# Connectors.net
KiCad netlist of a schematic drawn in Altium Designer
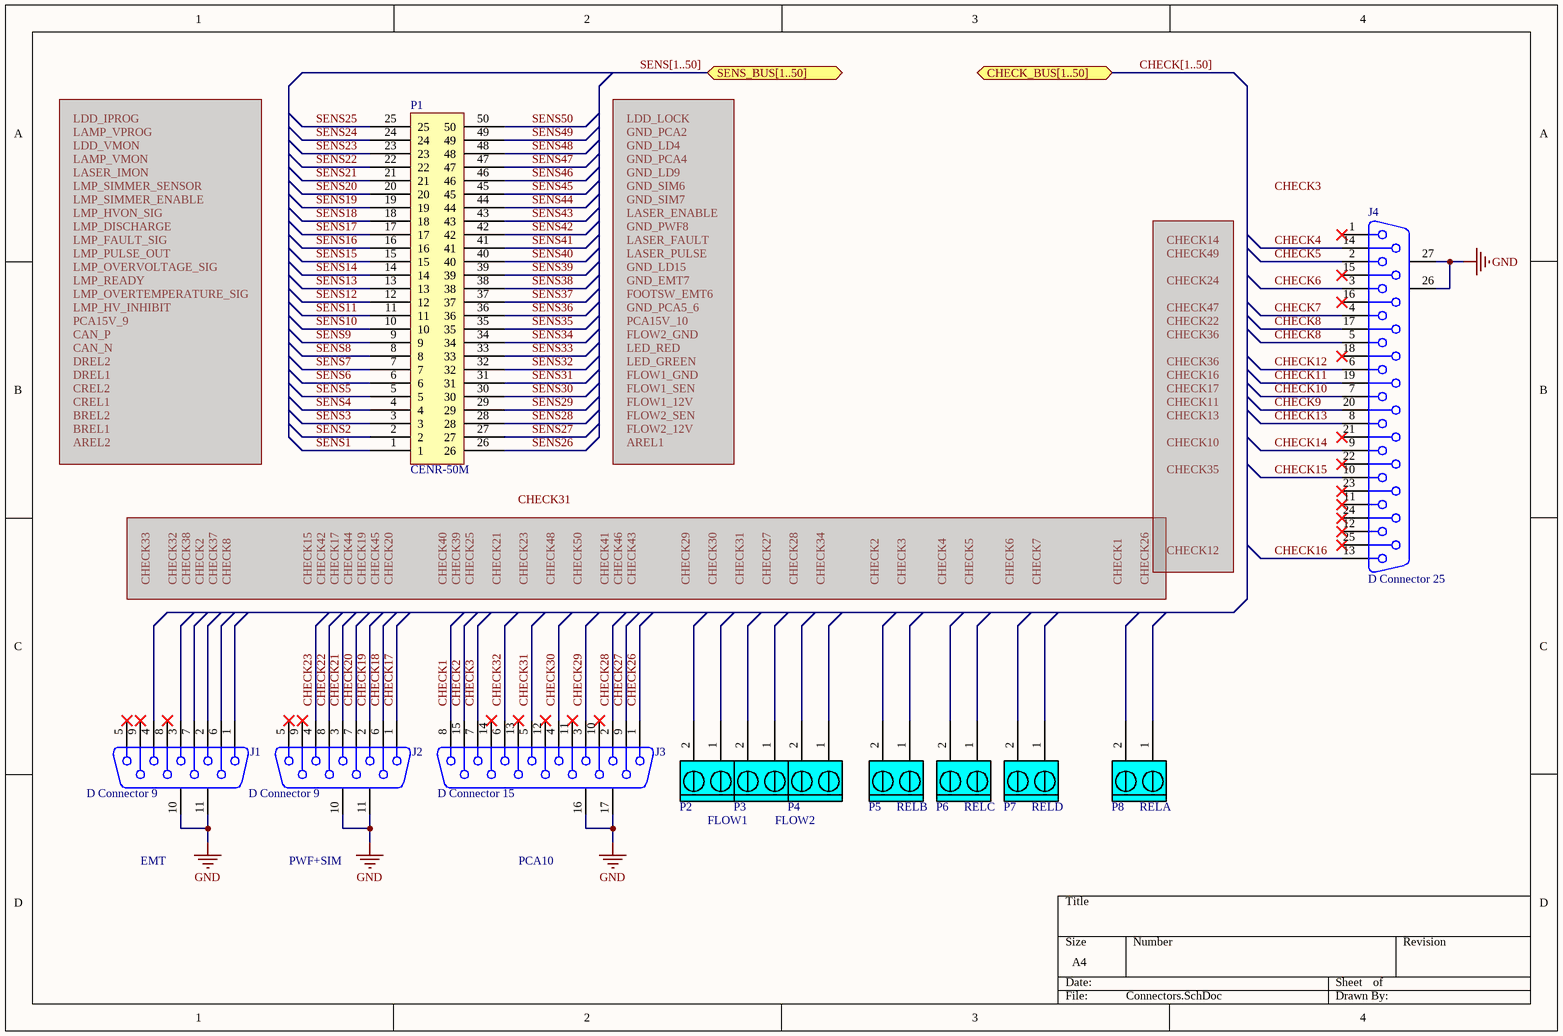
[diagram p0: Connectors.SchDoc]

(export (version "E")
  (design (tool "Eeschema 10.0.6"))
  (components
    (comp (ref "J1")
      (value "D Connector 9")
      (footprint "DSUB1.385-2H9F")
      (description "Receptacle Assembly, 9 Position, Right Angle")
      (fields (field (name "PUBLISHER") "Altium Limited"))
      (libsource (lib "Connectors") (part "D Connector 9"))
    )
    (comp (ref "J2")
      (value "D Connector 9")
      (footprint "DSUB1.385-2H9M")
      (description "Receptacle Assembly, 9 Position, Right Angle")
      (fields (field (name "PUBLISHER") "Altium Limited"))
      (libsource (lib "Connectors") (part "D Connector 9"))
    )
    (comp (ref "J3")
      (value "D Connector 15")
      (footprint "DSUB1.385-2H15M")
      (description "Receptacle Assembly, 15 Position, Right Angle")
      (fields (field (name "PUBLISHER") "Altium Limited"))
      (libsource (lib "Connectors") (part "D Connector 15"))
    )
    (comp (ref "J4")
      (value "D Connector 25")
      (footprint "DSUB1.385-2H25A-F")
      (description "Receptacle Assembly, 25 Position, Right Angle")
      (fields (field (name "PUBLISHER") "Altium Limited"))
      (libsource (lib "Connectors") (part "D Connector 25"))
    )
    (comp (ref "P1")
      (value "CENR-50M")
      (footprint "CENR-50M")
      (libsource (lib "Connectors") (part "CENR-50M"))
    )
    (comp (ref "P2")
      (value "DG340-3.81")
      (footprint "DG340-3.81-02P-00A(H)")
      (description "Terminal block")
      (libsource (lib "Connectors") (part "DG340-3.81-02P"))
    )
    (comp (ref "P3")
      (value "DG340-3.81")
      (footprint "DG340-3.81-02P-00A(H)")
      (description "Terminal block")
      (libsource (lib "Connectors") (part "DG340-3.81-02P"))
    )
    (comp (ref "P4")
      (value "DG340-3.81")
      (footprint "DG340-3.81-02P-00A(H)")
      (description "Terminal block")
      (libsource (lib "Connectors") (part "DG340-3.81-02P"))
    )
    (comp (ref "P5")
      (value "DG340-3.81")
      (footprint "DG340-3.81-02P-00A(H)")
      (description "Terminal block")
      (libsource (lib "Connectors") (part "DG340-3.81-02P"))
    )
    (comp (ref "P6")
      (value "DG340-3.81")
      (footprint "DG340-3.81-02P-00A(H)")
      (description "Terminal block")
      (libsource (lib "Connectors") (part "DG340-3.81-02P"))
    )
    (comp (ref "P7")
      (value "DG340-3.81")
      (footprint "DG340-3.81-02P-00A(H)")
      (description "Terminal block")
      (libsource (lib "Connectors") (part "DG340-3.81-02P"))
    )
    (comp (ref "P8")
      (value "DG340-3.81")
      (footprint "DG340-3.81-02P-00A(H)")
      (description "Terminal block")
      (libsource (lib "Connectors") (part "DG340-3.81-02P"))
    )
  )
  (nets
    (net (code "7") (name "/CHECK1") (class "Default")
      (node (ref "J3") (pin "8") (pinfunction "8_8") (pintype "passive"))
    )
    (net (code "8") (name "/CHECK2") (class "Default")
      (node (ref "J3") (pin "15") (pinfunction "15_15") (pintype "passive"))
    )
    (net (code "9") (name "/CHECK3") (class "Default")
      (node (ref "J3") (pin "7") (pinfunction "7_7") (pintype "passive"))
    )
    (net (code "10") (name "/CHECK4") (class "Default")
      (node (ref "J4") (pin "14") (pinfunction "14_14") (pintype "passive"))
    )
    (net (code "11") (name "/CHECK5") (class "Default")
      (node (ref "J4") (pin "2") (pinfunction "2_2") (pintype "passive"))
    )
    (net (code "12") (name "/CHECK6") (class "Default")
      (node (ref "J4") (pin "3") (pinfunction "3_3") (pintype "passive"))
    )
    (net (code "13") (name "/CHECK7") (class "Default")
      (node (ref "J4") (pin "4") (pinfunction "4_4") (pintype "passive"))
    )
    (net (code "14") (name "/CHECK8") (class "Default")
      (node (ref "J4") (pin "17") (pinfunction "17_17") (pintype "passive"))
      (node (ref "J4") (pin "5") (pinfunction "5_5") (pintype "passive"))
    )
    (net (code "15") (name "/CHECK9") (class "Default")
      (node (ref "J4") (pin "20") (pinfunction "20_20") (pintype "passive"))
    )
    (net (code "16") (name "/CHECK10") (class "Default")
      (node (ref "J4") (pin "7") (pinfunction "7_7") (pintype "passive"))
    )
    (net (code "17") (name "/CHECK11") (class "Default")
      (node (ref "J4") (pin "19") (pinfunction "19_19") (pintype "passive"))
    )
    (net (code "18") (name "/CHECK12") (class "Default")
      (node (ref "J4") (pin "6") (pinfunction "6_6") (pintype "passive"))
    )
    (net (code "19") (name "/CHECK13") (class "Default")
      (node (ref "J4") (pin "8") (pinfunction "8_8") (pintype "passive"))
    )
    (net (code "20") (name "/CHECK14") (class "Default")
      (node (ref "J4") (pin "9") (pinfunction "9_9") (pintype "passive"))
    )
    (net (code "21") (name "/CHECK15") (class "Default")
      (node (ref "J4") (pin "10") (pinfunction "10_10") (pintype "passive"))
    )
    (net (code "22") (name "/CHECK16") (class "Default")
      (node (ref "J4") (pin "13") (pinfunction "13_13") (pintype "passive"))
    )
    (net (code "23") (name "/CHECK17") (class "Default")
      (node (ref "J2") (pin "1") (pinfunction "1_1") (pintype "passive"))
    )
    (net (code "24") (name "/CHECK18") (class "Default")
      (node (ref "J2") (pin "6") (pinfunction "6_6") (pintype "passive"))
    )
    (net (code "25") (name "/CHECK19") (class "Default")
      (node (ref "J2") (pin "2") (pinfunction "2_2") (pintype "passive"))
    )
    (net (code "26") (name "/CHECK20") (class "Default")
      (node (ref "J2") (pin "7") (pinfunction "7_7") (pintype "passive"))
    )
    (net (code "27") (name "/CHECK21") (class "Default")
      (node (ref "J2") (pin "3") (pinfunction "3_3") (pintype "passive"))
    )
    (net (code "28") (name "/CHECK22") (class "Default")
      (node (ref "J2") (pin "8") (pinfunction "8_8") (pintype "passive"))
    )
    (net (code "29") (name "/CHECK23") (class "Default")
      (node (ref "J2") (pin "4") (pinfunction "4_4") (pintype "passive"))
    )
    (net (code "32") (name "/CHECK26") (class "Default")
      (node (ref "J3") (pin "1") (pinfunction "1_1") (pintype "passive"))
    )
    (net (code "33") (name "/CHECK27") (class "Default")
      (node (ref "J3") (pin "9") (pinfunction "9_9") (pintype "passive"))
    )
    (net (code "34") (name "/CHECK28") (class "Default")
      (node (ref "J3") (pin "2") (pinfunction "2_2") (pintype "passive"))
    )
    (net (code "35") (name "/CHECK29") (class "Default")
      (node (ref "J3") (pin "3") (pinfunction "3_3") (pintype "passive"))
    )
    (net (code "36") (name "/CHECK30") (class "Default")
      (node (ref "J3") (pin "4") (pinfunction "4_4") (pintype "passive"))
    )
    (net (code "37") (name "/CHECK31") (class "Default")
      (node (ref "J3") (pin "5") (pinfunction "5_5") (pintype "passive"))
    )
    (net (code "38") (name "/CHECK32") (class "Default")
      (node (ref "J3") (pin "6") (pinfunction "6_6") (pintype "passive"))
    )
    (net (code "102") (name "/SENS1") (class "Default")
      (node (ref "P1") (pin "1") (pinfunction "1_1") (pintype "passive"))
    )
    (net (code "103") (name "/SENS2") (class "Default")
      (node (ref "P1") (pin "2") (pinfunction "2_2") (pintype "passive"))
    )
    (net (code "104") (name "/SENS3") (class "Default")
      (node (ref "P1") (pin "3") (pinfunction "3_3") (pintype "passive"))
    )
    (net (code "105") (name "/SENS4") (class "Default")
      (node (ref "P1") (pin "4") (pinfunction "4_4") (pintype "passive"))
    )
    (net (code "106") (name "/SENS5") (class "Default")
      (node (ref "P1") (pin "5") (pinfunction "5_5") (pintype "passive"))
    )
    (net (code "107") (name "/SENS6") (class "Default")
      (node (ref "P1") (pin "6") (pinfunction "6_6") (pintype "passive"))
    )
    (net (code "108") (name "/SENS7") (class "Default")
      (node (ref "P1") (pin "7") (pinfunction "7_7") (pintype "passive"))
    )
    (net (code "109") (name "/SENS8") (class "Default")
      (node (ref "P1") (pin "8") (pinfunction "8_8") (pintype "passive"))
    )
    (net (code "110") (name "/SENS9") (class "Default")
      (node (ref "P1") (pin "9") (pinfunction "9_9") (pintype "passive"))
    )
    (net (code "111") (name "/SENS10") (class "Default")
      (node (ref "P1") (pin "10") (pinfunction "10_10") (pintype "passive"))
    )
    (net (code "112") (name "/SENS11") (class "Default")
      (node (ref "P1") (pin "11") (pinfunction "11_11") (pintype "passive"))
    )
    (net (code "113") (name "/SENS12") (class "Default")
      (node (ref "P1") (pin "12") (pinfunction "12_12") (pintype "passive"))
    )
    (net (code "114") (name "/SENS13") (class "Default")
      (node (ref "P1") (pin "13") (pinfunction "13_13") (pintype "passive"))
    )
    (net (code "115") (name "/SENS14") (class "Default")
      (node (ref "P1") (pin "14") (pinfunction "14_14") (pintype "passive"))
    )
    (net (code "116") (name "/SENS15") (class "Default")
      (node (ref "P1") (pin "15") (pinfunction "15_15") (pintype "passive"))
    )
    (net (code "117") (name "/SENS16") (class "Default")
      (node (ref "P1") (pin "16") (pinfunction "16_16") (pintype "passive"))
    )
    (net (code "118") (name "/SENS17") (class "Default")
      (node (ref "P1") (pin "17") (pinfunction "17_17") (pintype "passive"))
    )
    (net (code "119") (name "/SENS18") (class "Default")
      (node (ref "P1") (pin "18") (pinfunction "18_18") (pintype "passive"))
    )
    (net (code "120") (name "/SENS19") (class "Default")
      (node (ref "P1") (pin "19") (pinfunction "19_19") (pintype "passive"))
    )
    (net (code "121") (name "/SENS20") (class "Default")
      (node (ref "P1") (pin "20") (pinfunction "20_20") (pintype "passive"))
    )
    (net (code "122") (name "/SENS21") (class "Default")
      (node (ref "P1") (pin "21") (pinfunction "21_21") (pintype "passive"))
    )
    (net (code "123") (name "/SENS22") (class "Default")
      (node (ref "P1") (pin "22") (pinfunction "22_22") (pintype "passive"))
    )
    (net (code "124") (name "/SENS23") (class "Default")
      (node (ref "P1") (pin "23") (pinfunction "23_23") (pintype "passive"))
    )
    (net (code "125") (name "/SENS24") (class "Default")
      (node (ref "P1") (pin "24") (pinfunction "24_24") (pintype "passive"))
    )
    (net (code "126") (name "/SENS25") (class "Default")
      (node (ref "P1") (pin "25") (pinfunction "25_25") (pintype "passive"))
    )
    (net (code "127") (name "/SENS26") (class "Default")
      (node (ref "P1") (pin "26") (pinfunction "26_26") (pintype "passive"))
    )
    (net (code "128") (name "/SENS27") (class "Default")
      (node (ref "P1") (pin "27") (pinfunction "27_27") (pintype "passive"))
    )
    (net (code "129") (name "/SENS28") (class "Default")
      (node (ref "P1") (pin "28") (pinfunction "28_28") (pintype "passive"))
    )
    (net (code "130") (name "/SENS29") (class "Default")
      (node (ref "P1") (pin "29") (pinfunction "29_29") (pintype "passive"))
    )
    (net (code "131") (name "/SENS30") (class "Default")
      (node (ref "P1") (pin "30") (pinfunction "30_30") (pintype "passive"))
    )
    (net (code "132") (name "/SENS31") (class "Default")
      (node (ref "P1") (pin "31") (pinfunction "31_31") (pintype "passive"))
    )
    (net (code "133") (name "/SENS32") (class "Default")
      (node (ref "P1") (pin "32") (pinfunction "32_32") (pintype "passive"))
    )
    (net (code "134") (name "/SENS33") (class "Default")
      (node (ref "P1") (pin "33") (pinfunction "33_33") (pintype "passive"))
    )
    (net (code "135") (name "/SENS34") (class "Default")
      (node (ref "P1") (pin "34") (pinfunction "34_34") (pintype "passive"))
    )
    (net (code "136") (name "/SENS35") (class "Default")
      (node (ref "P1") (pin "35") (pinfunction "35_35") (pintype "passive"))
    )
    (net (code "137") (name "/SENS36") (class "Default")
      (node (ref "P1") (pin "36") (pinfunction "36_36") (pintype "passive"))
    )
    (net (code "138") (name "/SENS37") (class "Default")
      (node (ref "P1") (pin "37") (pinfunction "37_37") (pintype "passive"))
    )
    (net (code "139") (name "/SENS38") (class "Default")
      (node (ref "P1") (pin "38") (pinfunction "38_38") (pintype "passive"))
    )
    (net (code "140") (name "/SENS39") (class "Default")
      (node (ref "P1") (pin "39") (pinfunction "39_39") (pintype "passive"))
    )
    (net (code "141") (name "/SENS40") (class "Default")
      (node (ref "P1") (pin "40") (pinfunction "40_40") (pintype "passive"))
    )
    (net (code "142") (name "/SENS41") (class "Default")
      (node (ref "P1") (pin "41") (pinfunction "41_41") (pintype "passive"))
    )
    (net (code "143") (name "/SENS42") (class "Default")
      (node (ref "P1") (pin "42") (pinfunction "42_42") (pintype "passive"))
    )
    (net (code "144") (name "/SENS43") (class "Default")
      (node (ref "P1") (pin "43") (pinfunction "43_43") (pintype "passive"))
    )
    (net (code "145") (name "/SENS44") (class "Default")
      (node (ref "P1") (pin "44") (pinfunction "44_44") (pintype "passive"))
    )
    (net (code "146") (name "/SENS45") (class "Default")
      (node (ref "P1") (pin "45") (pinfunction "45_45") (pintype "passive"))
    )
    (net (code "147") (name "/SENS46") (class "Default")
      (node (ref "P1") (pin "46") (pinfunction "46_46") (pintype "passive"))
    )
    (net (code "148") (name "/SENS47") (class "Default")
      (node (ref "P1") (pin "47") (pinfunction "47_47") (pintype "passive"))
    )
    (net (code "149") (name "/SENS48") (class "Default")
      (node (ref "P1") (pin "48") (pinfunction "48_48") (pintype "passive"))
    )
    (net (code "150") (name "/SENS49") (class "Default")
      (node (ref "P1") (pin "49") (pinfunction "49_49") (pintype "passive"))
    )
    (net (code "151") (name "/SENS50") (class "Default")
      (node (ref "P1") (pin "50") (pinfunction "50_50") (pintype "passive"))
    )
    (net (code "153") (name "GND") (class "Default")
      (node (ref "J1") (pin "10") (pinfunction "MH1_10") (pintype "passive"))
      (node (ref "J1") (pin "11") (pinfunction "MH2_11") (pintype "passive"))
      (node (ref "J2") (pin "10") (pinfunction "MH1_10") (pintype "passive"))
      (node (ref "J2") (pin "11") (pinfunction "MH2_11") (pintype "passive"))
      (node (ref "J3") (pin "16") (pinfunction "MH1_16") (pintype "passive"))
      (node (ref "J3") (pin "17") (pinfunction "MH2_17") (pintype "passive"))
      (node (ref "J4") (pin "26") (pinfunction "MH1_26") (pintype "passive"))
      (node (ref "J4") (pin "27") (pinfunction "MH2_27") (pintype "passive"))
    )
    (net (code "154") (name "unconnected-(J1-Pad1)") (class "Default")
      (node (ref "J1") (pin "1") (pinfunction "1_1") (pintype "passive"))
    )
    (net (code "155") (name "unconnected-(J1-Pad2)") (class "Default")
      (node (ref "J1") (pin "2") (pinfunction "2_2") (pintype "passive"))
    )
    (net (code "156") (name "unconnected-(J1-Pad3)") (class "Default")
      (node (ref "J1") (pin "3") (pinfunction "3_3") (pintype "passive"))
    )
    (net (code "157") (name "unconnected-(J1-Pad4)") (class "Default")
      (node (ref "J1") (pin "4") (pinfunction "4_4") (pintype "passive"))
    )
    (net (code "158") (name "unconnected-(J1-Pad5)") (class "Default")
      (node (ref "J1") (pin "5") (pinfunction "5_5") (pintype "passive+no_connect"))
    )
    (net (code "159") (name "unconnected-(J1-Pad6)") (class "Default")
      (node (ref "J1") (pin "6") (pinfunction "6_6") (pintype "passive"))
    )
    (net (code "160") (name "unconnected-(J1-Pad7)") (class "Default")
      (node (ref "J1") (pin "7") (pinfunction "7_7") (pintype "passive"))
    )
    (net (code "161") (name "unconnected-(J1-Pad8)") (class "Default")
      (node (ref "J1") (pin "8") (pinfunction "8_8") (pintype "passive+no_connect"))
    )
    (net (code "162") (name "unconnected-(J1-Pad9)") (class "Default")
      (node (ref "J1") (pin "9") (pinfunction "9_9") (pintype "passive+no_connect"))
    )
    (net (code "163") (name "unconnected-(J2-Pad5)") (class "Default")
      (node (ref "J2") (pin "5") (pinfunction "5_5") (pintype "passive+no_connect"))
    )
    (net (code "164") (name "unconnected-(J2-Pad9)") (class "Default")
      (node (ref "J2") (pin "9") (pinfunction "9_9") (pintype "passive+no_connect"))
    )
    (net (code "165") (name "unconnected-(J3-Pad10)") (class "Default")
      (node (ref "J3") (pin "10") (pinfunction "10_10") (pintype "passive+no_connect"))
    )
    (net (code "166") (name "unconnected-(J3-Pad11)") (class "Default")
      (node (ref "J3") (pin "11") (pinfunction "11_11") (pintype "passive+no_connect"))
    )
    (net (code "167") (name "unconnected-(J3-Pad12)") (class "Default")
      (node (ref "J3") (pin "12") (pinfunction "12_12") (pintype "passive+no_connect"))
    )
    (net (code "168") (name "unconnected-(J3-Pad13)") (class "Default")
      (node (ref "J3") (pin "13") (pinfunction "13_13") (pintype "passive+no_connect"))
    )
    (net (code "169") (name "unconnected-(J3-Pad14)") (class "Default")
      (node (ref "J3") (pin "14") (pinfunction "14_14") (pintype "passive+no_connect"))
    )
    (net (code "170") (name "unconnected-(J4-Pad1)") (class "Default")
      (node (ref "J4") (pin "1") (pinfunction "1_1") (pintype "passive+no_connect"))
    )
    (net (code "171") (name "unconnected-(J4-Pad11)") (class "Default")
      (node (ref "J4") (pin "11") (pinfunction "11_11") (pintype "passive+no_connect"))
    )
    (net (code "172") (name "unconnected-(J4-Pad12)") (class "Default")
      (node (ref "J4") (pin "12") (pinfunction "12_12") (pintype "passive+no_connect"))
    )
    (net (code "173") (name "unconnected-(J4-Pad15)") (class "Default")
      (node (ref "J4") (pin "15") (pinfunction "15_15") (pintype "passive+no_connect"))
    )
    (net (code "174") (name "unconnected-(J4-Pad16)") (class "Default")
      (node (ref "J4") (pin "16") (pinfunction "16_16") (pintype "passive+no_connect"))
    )
    (net (code "175") (name "unconnected-(J4-Pad18)") (class "Default")
      (node (ref "J4") (pin "18") (pinfunction "18_18") (pintype "passive+no_connect"))
    )
    (net (code "176") (name "unconnected-(J4-Pad21)") (class "Default")
      (node (ref "J4") (pin "21") (pinfunction "21_21") (pintype "passive+no_connect"))
    )
    (net (code "177") (name "unconnected-(J4-Pad22)") (class "Default")
      (node (ref "J4") (pin "22") (pinfunction "22_22") (pintype "passive+no_connect"))
    )
    (net (code "178") (name "unconnected-(J4-Pad23)") (class "Default")
      (node (ref "J4") (pin "23") (pinfunction "23_23") (pintype "passive+no_connect"))
    )
    (net (code "179") (name "unconnected-(J4-Pad24)") (class "Default")
      (node (ref "J4") (pin "24") (pinfunction "24_24") (pintype "passive+no_connect"))
    )
    (net (code "180") (name "unconnected-(J4-Pad25)") (class "Default")
      (node (ref "J4") (pin "25") (pinfunction "25_25") (pintype "passive+no_connect"))
    )
    (net (code "181") (name "unconnected-(P2-Pad1)") (class "Default")
      (node (ref "P2") (pin "1") (pinfunction "1_1") (pintype "passive"))
    )
    (net (code "182") (name "unconnected-(P2-Pad2)") (class "Default")
      (node (ref "P2") (pin "2") (pinfunction "2_2") (pintype "passive"))
    )
    (net (code "183") (name "unconnected-(P3-Pad1)") (class "Default")
      (node (ref "P3") (pin "1") (pinfunction "1_1") (pintype "passive"))
    )
    (net (code "184") (name "unconnected-(P3-Pad2)") (class "Default")
      (node (ref "P3") (pin "2") (pinfunction "2_2") (pintype "passive"))
    )
    (net (code "185") (name "unconnected-(P4-Pad1)") (class "Default")
      (node (ref "P4") (pin "1") (pinfunction "1_1") (pintype "passive"))
    )
    (net (code "186") (name "unconnected-(P4-Pad2)") (class "Default")
      (node (ref "P4") (pin "2") (pinfunction "2_2") (pintype "passive"))
    )
    (net (code "187") (name "unconnected-(P5-Pad1)") (class "Default")
      (node (ref "P5") (pin "1") (pinfunction "1_1") (pintype "passive"))
    )
    (net (code "188") (name "unconnected-(P5-Pad2)") (class "Default")
      (node (ref "P5") (pin "2") (pinfunction "2_2") (pintype "passive"))
    )
    (net (code "189") (name "unconnected-(P6-Pad1)") (class "Default")
      (node (ref "P6") (pin "1") (pinfunction "1_1") (pintype "passive"))
    )
    (net (code "190") (name "unconnected-(P6-Pad2)") (class "Default")
      (node (ref "P6") (pin "2") (pinfunction "2_2") (pintype "passive"))
    )
    (net (code "191") (name "unconnected-(P7-Pad1)") (class "Default")
      (node (ref "P7") (pin "1") (pinfunction "1_1") (pintype "passive"))
    )
    (net (code "192") (name "unconnected-(P7-Pad2)") (class "Default")
      (node (ref "P7") (pin "2") (pinfunction "2_2") (pintype "passive"))
    )
    (net (code "193") (name "unconnected-(P8-Pad1)") (class "Default")
      (node (ref "P8") (pin "1") (pinfunction "1_1") (pintype "passive"))
    )
    (net (code "194") (name "unconnected-(P8-Pad2)") (class "Default")
      (node (ref "P8") (pin "2") (pinfunction "2_2") (pintype "passive"))
    )
  )
)
